# rapidshark-main-breakout-top-mk-1_6.net
KiCad netlist of a schematic drawn in EAGLE
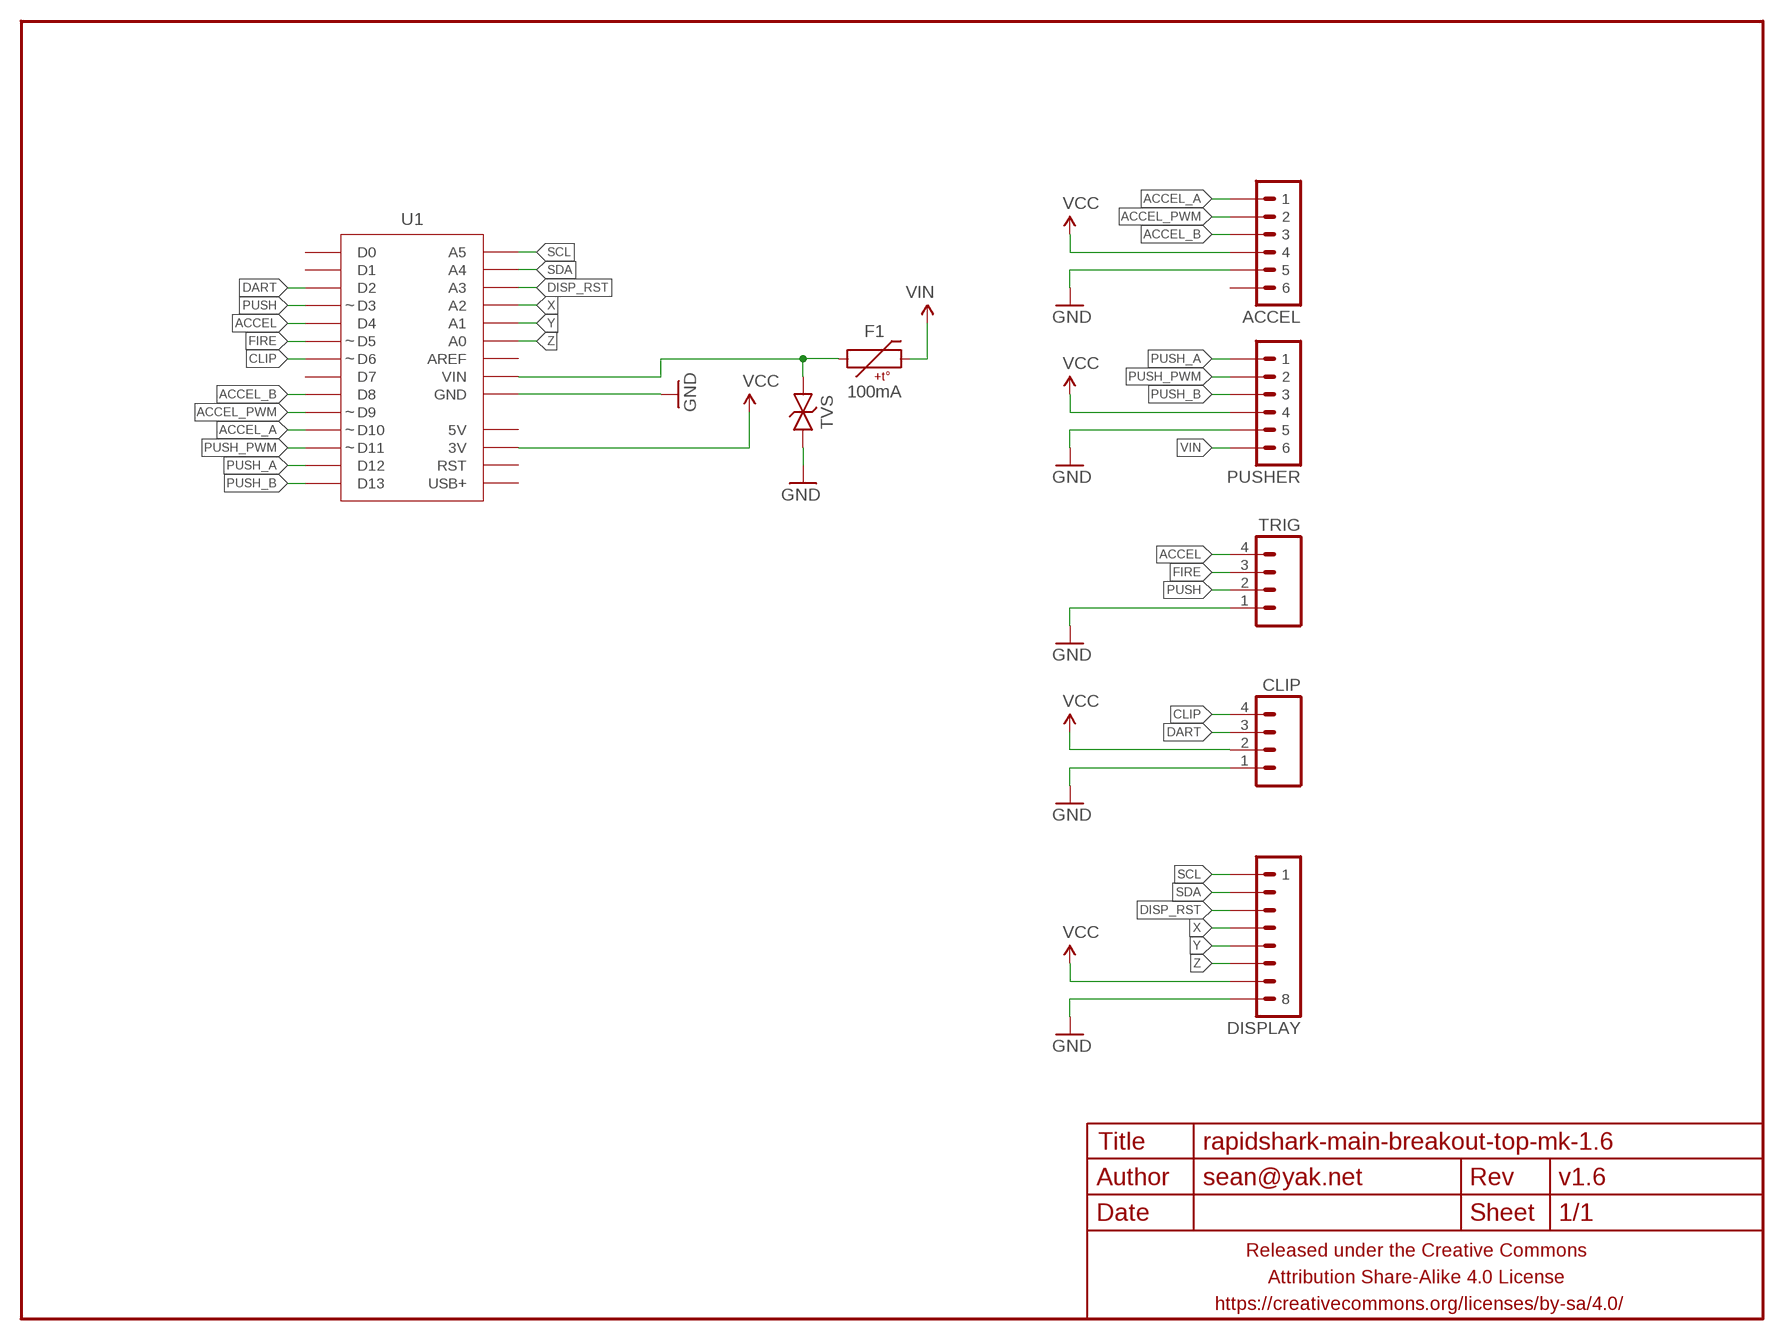
[diagram p0: schematic, sheet 1]

(export (version "E")
  (design (tool "Eeschema 10.0.6"))
  (components
    (comp (ref "ACCEL")
      (value "M06JST-PH-PTH-VERT")
      (footprint "eagle-import:JST-6-PH-VERT-PTH")
      (libsource (lib "eagle-import") (part "M06JST-PH-PTH-VERT"))
    )
    (comp (ref "CLIP")
      (value "M04JST-PTH-VERT")
      (footprint "eagle-import:JST-4-PH-VERT-PTH")
      (libsource (lib "eagle-import") (part "M04JST-PTH-VERT"))
    )
    (comp (ref "DISPLAY")
      (value "M08JST-PH-VERT-PTH")
      (footprint "eagle-import:JST-8-VERT-PTH")
      (libsource (lib "eagle-import") (part "M08JST-PH-VERT-PTH"))
    )
    (comp (ref "F1")
      (value "100mA")
      (footprint "eagle-import:PTC-1206")
      (libsource (lib "eagle-import") (part "PTCSMD"))
    )
    (comp (ref "FRAME1")
      (value "FRAME-LETTERNO_PACKAGE")
      (footprint "eagle-import:DUMMY")
      (fields (field (name "DESIGNER") "sean@yak.net") (field (name "VERSION") "v1.6"))
      (libsource (lib "eagle-import") (part "FRAME-LETTERNO_PACKAGE"))
    )
    (comp (ref "PUSHER")
      (value "M06JST-PH-PTH-VERT")
      (footprint "eagle-import:JST-6-PH-VERT-PTH")
      (libsource (lib "eagle-import") (part "M06JST-PH-PTH-VERT"))
    )
    (comp (ref "TRIG")
      (value "M04JST-PTH-VERT")
      (footprint "eagle-import:JST-4-PH-VERT-PTH")
      (libsource (lib "eagle-import") (part "M04JST-PTH-VERT"))
    )
    (comp (ref "TVS")
      (value "TVSSMA")
      (footprint "eagle-import:SMA-DIODE-TVS-BIDIR")
      (libsource (lib "eagle-import") (part "TVSSMA"))
    )
    (comp (ref "U1")
      (value "ADAFRUIT_METRO_MININOSILK-AMBI2")
      (footprint "eagle-import:ADAFRUIT_METRO_MINI_BACK")
      (libsource (lib "eagle-import") (part "ADAFRUIT_METRO_MININOSILK-AMBI2"))
    )
  )
  (nets
    (net (code "1") (name "ACCEL") (class "Default")
      (node (ref "TRIG") (pin "4") (pinfunction "4_4") (pintype "passive"))
      (node (ref "U1") (pin "5") (pinfunction "D4_5") (pintype "bidirectional"))
    )
    (net (code "2") (name "ACCEL_A") (class "Default")
      (node (ref "ACCEL") (pin "1") (pinfunction "1_1") (pintype "passive"))
      (node (ref "U1") (pin "11") (pinfunction "D10_11") (pintype "bidirectional"))
    )
    (net (code "3") (name "ACCEL_B") (class "Default")
      (node (ref "ACCEL") (pin "3") (pinfunction "3_3") (pintype "passive"))
      (node (ref "U1") (pin "9") (pinfunction "D8_9") (pintype "bidirectional"))
    )
    (net (code "4") (name "ACCEL_PWM") (class "Default")
      (node (ref "ACCEL") (pin "2") (pinfunction "2_2") (pintype "passive"))
      (node (ref "U1") (pin "10") (pinfunction "D9_10") (pintype "bidirectional"))
    )
    (net (code "5") (name "CLIP") (class "Default")
      (node (ref "CLIP") (pin "4") (pinfunction "4_4") (pintype "passive"))
      (node (ref "U1") (pin "7") (pinfunction "D6_7") (pintype "bidirectional"))
    )
    (net (code "6") (name "DART") (class "Default")
      (node (ref "CLIP") (pin "3") (pinfunction "3_3") (pintype "passive"))
      (node (ref "U1") (pin "3") (pinfunction "D2_3") (pintype "bidirectional"))
    )
    (net (code "7") (name "DISP_RST") (class "Default")
      (node (ref "DISPLAY") (pin "3") (pinfunction "3_3") (pintype "passive"))
      (node (ref "U1") (pin "26") (pinfunction "A3_26") (pintype "bidirectional"))
    )
    (net (code "8") (name "FIRE") (class "Default")
      (node (ref "TRIG") (pin "3") (pinfunction "3_3") (pintype "passive"))
      (node (ref "U1") (pin "6") (pinfunction "D5_6") (pintype "bidirectional"))
    )
    (net (code "9") (name "GND") (class "Default")
      (node (ref "ACCEL") (pin "5") (pinfunction "5_5") (pintype "passive"))
      (node (ref "CLIP") (pin "1") (pinfunction "1_1") (pintype "passive"))
      (node (ref "DISPLAY") (pin "8") (pinfunction "8_8") (pintype "passive"))
      (node (ref "PUSHER") (pin "5") (pinfunction "5_5") (pintype "passive"))
      (node (ref "TRIG") (pin "1") (pinfunction "1_1") (pintype "passive"))
      (node (ref "TVS") (pin "1") (pinfunction "1_1") (pintype "passive"))
      (node (ref "U1") (pin "19") (pinfunction "GND_19") (pintype "bidirectional"))
      (node (ref "U1") (pin "20") (pinfunction "GND_20") (pintype "bidirectional"))
    )
    (net (code "10") (name "Net-(U1-VIN)") (class "Default")
      (node (ref "F1") (pin "1") (pinfunction "1_1") (pintype "passive"))
      (node (ref "TVS") (pin "2") (pinfunction "2_2") (pintype "passive"))
      (node (ref "U1") (pin "21") (pinfunction "VIN_21") (pintype "bidirectional"))
    )
    (net (code "11") (name "PUSH") (class "Default")
      (node (ref "TRIG") (pin "2") (pinfunction "2_2") (pintype "passive"))
      (node (ref "U1") (pin "4") (pinfunction "D3_4") (pintype "bidirectional"))
    )
    (net (code "12") (name "PUSH_A") (class "Default")
      (node (ref "PUSHER") (pin "1") (pinfunction "1_1") (pintype "passive"))
      (node (ref "U1") (pin "13") (pinfunction "D12_13") (pintype "bidirectional"))
    )
    (net (code "13") (name "PUSH_B") (class "Default")
      (node (ref "PUSHER") (pin "3") (pinfunction "3_3") (pintype "passive"))
      (node (ref "U1") (pin "14") (pinfunction "D13_14") (pintype "bidirectional"))
    )
    (net (code "14") (name "PUSH_PWM") (class "Default")
      (node (ref "PUSHER") (pin "2") (pinfunction "2_2") (pintype "passive"))
      (node (ref "U1") (pin "12") (pinfunction "D11_12") (pintype "bidirectional"))
    )
    (net (code "15") (name "SCL") (class "Default")
      (node (ref "DISPLAY") (pin "1") (pinfunction "1_1") (pintype "passive"))
      (node (ref "U1") (pin "28") (pinfunction "A5_28") (pintype "bidirectional"))
    )
    (net (code "16") (name "SDA") (class "Default")
      (node (ref "DISPLAY") (pin "2") (pinfunction "2_2") (pintype "passive"))
      (node (ref "U1") (pin "27") (pinfunction "A4_27") (pintype "bidirectional"))
    )
    (net (code "17") (name "VCC") (class "Default")
      (node (ref "ACCEL") (pin "4") (pinfunction "4_4") (pintype "passive"))
      (node (ref "CLIP") (pin "2") (pinfunction "2_2") (pintype "passive"))
      (node (ref "DISPLAY") (pin "7") (pinfunction "7_7") (pintype "passive"))
      (node (ref "PUSHER") (pin "4") (pinfunction "4_4") (pintype "passive"))
      (node (ref "U1") (pin "17") (pinfunction "3V_17") (pintype "bidirectional"))
    )
    (net (code "18") (name "VIN") (class "Default")
      (node (ref "F1") (pin "2") (pinfunction "2_2") (pintype "passive"))
      (node (ref "PUSHER") (pin "6") (pinfunction "6_6") (pintype "passive"))
    )
    (net (code "19") (name "X") (class "Default")
      (node (ref "DISPLAY") (pin "4") (pinfunction "4_4") (pintype "passive"))
      (node (ref "U1") (pin "25") (pinfunction "A2_25") (pintype "bidirectional"))
    )
    (net (code "20") (name "Y") (class "Default")
      (node (ref "DISPLAY") (pin "5") (pinfunction "5_5") (pintype "passive"))
      (node (ref "U1") (pin "24") (pinfunction "A1_24") (pintype "bidirectional"))
    )
    (net (code "21") (name "Z") (class "Default")
      (node (ref "DISPLAY") (pin "6") (pinfunction "6_6") (pintype "passive"))
      (node (ref "U1") (pin "23") (pinfunction "A0_23") (pintype "bidirectional"))
    )
    (net (code "22") (name "unconnected-(ACCEL-Pad6)") (class "Default")
      (node (ref "ACCEL") (pin "6") (pinfunction "6_6") (pintype "passive"))
    )
    (net (code "23") (name "unconnected-(U1-5V-Pad18)") (class "Default")
      (node (ref "U1") (pin "18") (pinfunction "5V_18") (pintype "bidirectional"))
    )
    (net (code "24") (name "unconnected-(U1-AREF-Pad22)") (class "Default")
      (node (ref "U1") (pin "22") (pinfunction "AREF_22") (pintype "bidirectional"))
    )
    (net (code "25") (name "unconnected-(U1-D0-Pad1)") (class "Default")
      (node (ref "U1") (pin "1") (pinfunction "D0_1") (pintype "bidirectional"))
    )
    (net (code "26") (name "unconnected-(U1-D1-Pad2)") (class "Default")
      (node (ref "U1") (pin "2") (pinfunction "D1_2") (pintype "bidirectional"))
    )
    (net (code "27") (name "unconnected-(U1-D7-Pad8)") (class "Default")
      (node (ref "U1") (pin "8") (pinfunction "D7_8") (pintype "bidirectional"))
    )
    (net (code "28") (name "unconnected-(U1-RST-Pad16)") (class "Default")
      (node (ref "U1") (pin "16") (pinfunction "RST_16") (pintype "bidirectional"))
    )
    (net (code "29") (name "unconnected-(U1-USB+-Pad15)") (class "Default")
      (node (ref "U1") (pin "15") (pinfunction "USB+_15") (pintype "bidirectional"))
    )
  )
)
